# buckboost_fixed.net
KiCad netlist of a schematic drawn in Altium Designer
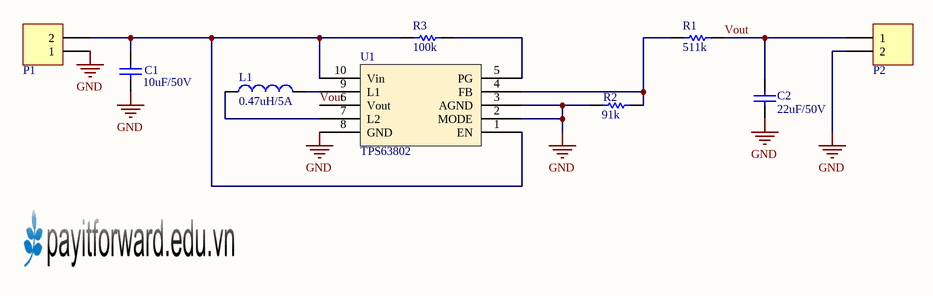
[diagram p0: buckboost fixed.SchDoc]

(export (version "E")
  (design (tool "Eeschema 10.0.6"))
  (components
    (comp (ref "C1")
      (value "10uF/50V")
      (footprint "CAP-SM-0603")
      (description "Capacitor")
      (fields (field (name "Comment") "Cap Non-Pol SMD"))
      (libsource (lib "PIF_Library") (part "Cap Non-Pol SMD"))
    )
    (comp (ref "C2")
      (value "22uF/50V")
      (footprint "CAP-SM-0603")
      (description "Capacitor")
      (fields (field (name "Comment") "Cap Non-Pol SMD"))
      (libsource (lib "PIF_Library") (part "Cap Non-Pol SMD"))
    )
    (comp (ref "L1")
      (value "0.47uH/5A")
      (footprint "INDUCTOR 12.5x12.5")
      (description "Inductor")
      (libsource (lib "PIF_Library") (part "Inductor"))
    )
    (comp (ref "LOGO1")
      (value "LOGO PIF")
      (footprint "PIF LOGO BIG SSTOP")
      (libsource (lib "PIF_Library") (part "LOGO PIF"))
    )
    (comp (ref "P1")
      (value "Domino 2")
      (footprint "DOMINO 2- 5mm")
      (description "Domino, 2-Pin")
      (fields (field (name "PUBLISHER") "Altium Limited"))
      (libsource (lib "PIF_Library") (part "Domino 2"))
    )
    (comp (ref "P2")
      (value "Domino 2")
      (footprint "DOMINO 2- 5mm")
      (description "Domino, 2-Pin")
      (fields (field (name "PUBLISHER") "Altium Limited"))
      (libsource (lib "") (part "Domino 2_1"))
    )
    (comp (ref "R1")
      (value "511k")
      (footprint "RES-SM-0805")
      (description "Resistor")
      (fields (field (name "Comment") "RESISTOR SMD"))
      (libsource (lib "PIF_Library") (part "RESISTOR SMD"))
    )
    (comp (ref "R2")
      (value "91k")
      (footprint "RES-SM-0805")
      (description "Resistor")
      (fields (field (name "Comment") "RESISTOR SMD"))
      (libsource (lib "PIF_Library") (part "RESISTOR SMD"))
    )
    (comp (ref "R3")
      (value "100k")
      (footprint "RES-SM-0805")
      (description "Resistor")
      (fields (field (name "Comment") "RESISTOR SMD"))
      (libsource (lib "PIF_Library") (part "RESISTOR SMD"))
    )
    (comp (ref "U1")
      (value "TPS63802")
      (footprint "TPS63802")
      (description "SMD")
      (libsource (lib "buck&boost") (part "TPS63802"))
    )
  )
  (nets
    (net (code "1") (name "/Vout") (class "Default")
      (node (ref "C2") (pin "2") (pinfunction "2_2") (pintype "passive"))
      (node (ref "P2") (pin "1") (pinfunction "1_1") (pintype "passive"))
      (node (ref "R1") (pin "2") (pinfunction "2_2") (pintype "passive"))
      (node (ref "U1") (pin "6") (pinfunction "Vout_6") (pintype "passive"))
    )
    (net (code "2") (name "GND") (class "Default")
      (node (ref "C1") (pin "1") (pinfunction "1_1") (pintype "passive"))
      (node (ref "C2") (pin "1") (pinfunction "1_1") (pintype "passive"))
      (node (ref "P1") (pin "1") (pinfunction "1_1") (pintype "passive"))
      (node (ref "P2") (pin "2") (pinfunction "2_2") (pintype "passive"))
      (node (ref "R2") (pin "2") (pinfunction "2_2") (pintype "passive"))
      (node (ref "U1") (pin "2") (pinfunction "MODE_2") (pintype "passive"))
      (node (ref "U1") (pin "3") (pinfunction "AGND_3") (pintype "passive"))
      (node (ref "U1") (pin "8") (pinfunction "GND_8") (pintype "passive"))
    )
    (net (code "3") (name "Net-(U1-EN)") (class "Default")
      (node (ref "C1") (pin "2") (pinfunction "2_2") (pintype "passive"))
      (node (ref "P1") (pin "2") (pinfunction "2_2") (pintype "passive"))
      (node (ref "R3") (pin "1") (pinfunction "1_1") (pintype "passive"))
      (node (ref "U1") (pin "1") (pinfunction "EN_1") (pintype "passive"))
      (node (ref "U1") (pin "10") (pinfunction "Vin_10") (pintype "passive"))
    )
    (net (code "4") (name "Net-(U1-FB)") (class "Default")
      (node (ref "R1") (pin "1") (pinfunction "1_1") (pintype "passive"))
      (node (ref "R2") (pin "1") (pinfunction "1_1") (pintype "passive"))
      (node (ref "U1") (pin "4") (pinfunction "FB_4") (pintype "passive"))
    )
    (net (code "5") (name "Net-(U1-L1)") (class "Default")
      (node (ref "L1") (pin "2") (pinfunction "2_2") (pintype "passive"))
      (node (ref "U1") (pin "9") (pinfunction "L1_9") (pintype "passive"))
    )
    (net (code "6") (name "Net-(U1-L2)") (class "Default")
      (node (ref "L1") (pin "1") (pinfunction "1_1") (pintype "passive"))
      (node (ref "U1") (pin "7") (pinfunction "L2_7") (pintype "passive"))
    )
    (net (code "7") (name "Net-(U1-PG)") (class "Default")
      (node (ref "R3") (pin "2") (pinfunction "2_2") (pintype "passive"))
      (node (ref "U1") (pin "5") (pinfunction "PG_5") (pintype "passive"))
    )
  )
)
